# Schematic.net
KiCad netlist of a schematic drawn in Altium Designer
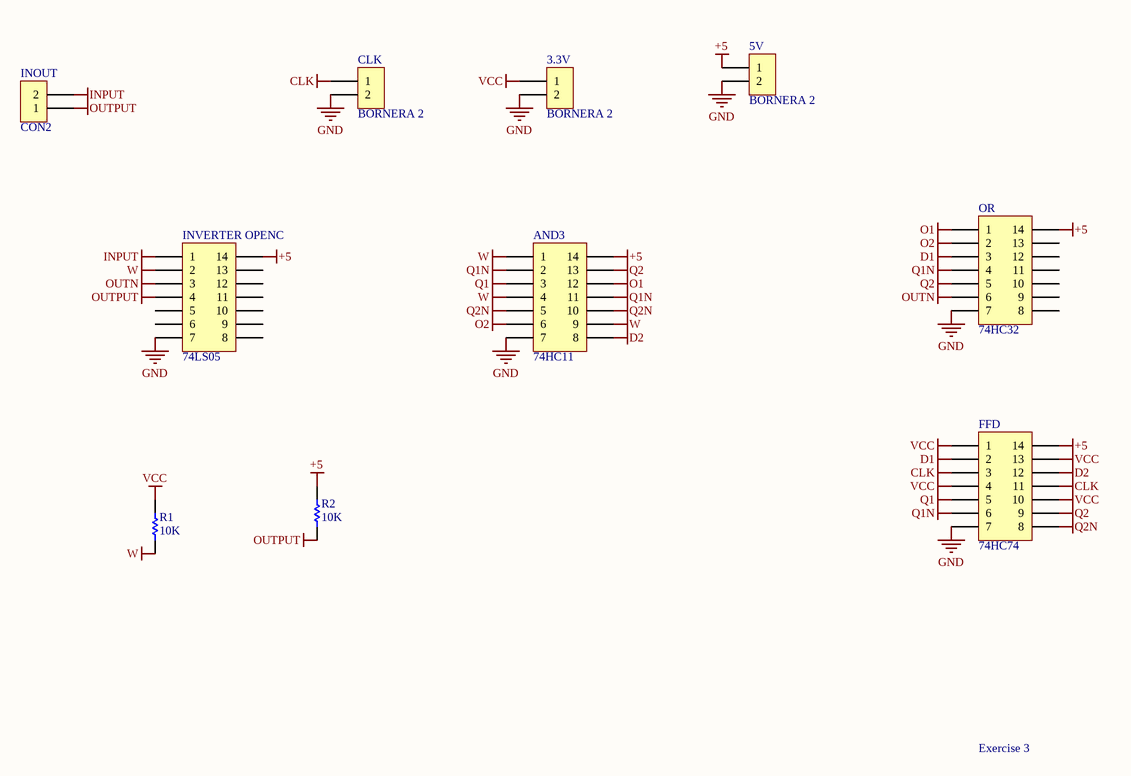
[diagram p0: Schematic.SchDoc]

(export (version "E")
  (design (tool "Eeschema 10.0.6"))
  (components
    (comp (ref "3.3V")
      (value "BORNERA 2")
      (footprint "BORNERA2")
      (libsource (lib "LIBEBAL") (part "BORNERA 2"))
    )
    (comp (ref "5V")
      (value "BORNERA 2")
      (footprint "BORNERA2")
      (libsource (lib "LIBEBAL") (part "BORNERA 2"))
    )
    (comp (ref "AND3") (value "74HC11") (footprint "DIP14") (libsource (lib "LIBEBAL") (part "IC_DIP14")))
    (comp (ref "CLK")
      (value "BORNERA 2")
      (footprint "BORNERA2")
      (libsource (lib "LIBEBAL") (part "BORNERA 2"))
    )
    (comp (ref "FFD") (value "74HC74") (footprint "DIP14") (libsource (lib "LIBEBAL") (part "IC_DIP14")))
    (comp (ref "INOUT") (value "CON2") (footprint "SIP2") (libsource (lib "LIBEBAL") (part "CON2")))
    (comp (ref "INVERTER OPENC")
      (value "74LS05")
      (footprint "DIP14")
      (libsource (lib "LIBEBAL") (part "IC_DIP14"))
    )
    (comp (ref "OR") (value "74HC32") (footprint "DIP14") (libsource (lib "LIBEBAL") (part "IC_DIP14")))
    (comp (ref "R1") (value "10K") (footprint "RES400") (libsource (lib "LIBEBAL") (part "RES")))
    (comp (ref "R2") (value "10K") (footprint "RES400") (libsource (lib "LIBEBAL") (part "RES")))
  )
  (nets
    (net (code "1") (name "+5") (class "Default")
      (node (ref "5V") (pin "1") (pinfunction "1_1") (pintype "passive"))
      (node (ref "AND3") (pin "14") (pinfunction "14_14") (pintype "passive"))
      (node (ref "FFD") (pin "14") (pinfunction "14_14") (pintype "passive"))
      (node (ref "INVERTER OPENC") (pin "14") (pinfunction "14_14") (pintype "passive"))
      (node (ref "OR") (pin "14") (pinfunction "14_14") (pintype "passive"))
      (node (ref "R2") (pin "2") (pinfunction "2_2") (pintype "passive"))
    )
    (net (code "2") (name "CLK") (class "Default")
      (node (ref "CLK") (pin "1") (pinfunction "1_1") (pintype "passive"))
      (node (ref "FFD") (pin "11") (pinfunction "11_11") (pintype "passive"))
      (node (ref "FFD") (pin "3") (pinfunction "3_3") (pintype "passive"))
    )
    (net (code "3") (name "D1") (class "Default")
      (node (ref "FFD") (pin "2") (pinfunction "2_2") (pintype "passive"))
      (node (ref "OR") (pin "3") (pinfunction "3_3") (pintype "passive"))
    )
    (net (code "4") (name "D2") (class "Default")
      (node (ref "AND3") (pin "8") (pinfunction "8_8") (pintype "passive"))
      (node (ref "FFD") (pin "12") (pinfunction "12_12") (pintype "passive"))
    )
    (net (code "5") (name "GND") (class "Default")
      (node (ref "3.3V") (pin "2") (pinfunction "2_2") (pintype "passive"))
      (node (ref "5V") (pin "2") (pinfunction "2_2") (pintype "passive"))
      (node (ref "AND3") (pin "7") (pinfunction "7_7") (pintype "passive"))
      (node (ref "CLK") (pin "2") (pinfunction "2_2") (pintype "passive"))
      (node (ref "FFD") (pin "7") (pinfunction "7_7") (pintype "passive"))
      (node (ref "INVERTER OPENC") (pin "7") (pinfunction "7_7") (pintype "passive"))
      (node (ref "OR") (pin "7") (pinfunction "7_7") (pintype "passive"))
    )
    (net (code "6") (name "INPUT") (class "Default")
      (node (ref "INOUT") (pin "2") (pinfunction "2_2") (pintype "passive"))
      (node (ref "INVERTER OPENC") (pin "1") (pinfunction "1_1") (pintype "passive"))
    )
    (net (code "7") (name "O1") (class "Default")
      (node (ref "AND3") (pin "12") (pinfunction "12_12") (pintype "passive"))
      (node (ref "OR") (pin "1") (pinfunction "1_1") (pintype "passive"))
    )
    (net (code "8") (name "O2") (class "Default")
      (node (ref "AND3") (pin "6") (pinfunction "6_6") (pintype "passive"))
      (node (ref "OR") (pin "2") (pinfunction "2_2") (pintype "passive"))
    )
    (net (code "9") (name "OUTN") (class "Default")
      (node (ref "INVERTER OPENC") (pin "3") (pinfunction "3_3") (pintype "passive"))
      (node (ref "OR") (pin "6") (pinfunction "6_6") (pintype "passive"))
    )
    (net (code "10") (name "OUTPUT") (class "Default")
      (node (ref "INOUT") (pin "1") (pinfunction "1_1") (pintype "passive"))
      (node (ref "INVERTER OPENC") (pin "4") (pinfunction "4_4") (pintype "passive"))
      (node (ref "R2") (pin "1") (pinfunction "1_1") (pintype "passive"))
    )
    (net (code "11") (name "Q1") (class "Default")
      (node (ref "AND3") (pin "3") (pinfunction "3_3") (pintype "passive"))
      (node (ref "FFD") (pin "5") (pinfunction "5_5") (pintype "passive"))
    )
    (net (code "12") (name "Q1N") (class "Default")
      (node (ref "AND3") (pin "11") (pinfunction "11_11") (pintype "passive"))
      (node (ref "AND3") (pin "2") (pinfunction "2_2") (pintype "passive"))
      (node (ref "FFD") (pin "6") (pinfunction "6_6") (pintype "passive"))
      (node (ref "OR") (pin "4") (pinfunction "4_4") (pintype "passive"))
    )
    (net (code "13") (name "Q2") (class "Default")
      (node (ref "AND3") (pin "13") (pinfunction "13_13") (pintype "passive"))
      (node (ref "FFD") (pin "9") (pinfunction "9_9") (pintype "passive"))
      (node (ref "OR") (pin "5") (pinfunction "5_5") (pintype "passive"))
    )
    (net (code "14") (name "Q2N") (class "Default")
      (node (ref "AND3") (pin "10") (pinfunction "10_10") (pintype "passive"))
      (node (ref "AND3") (pin "5") (pinfunction "5_5") (pintype "passive"))
      (node (ref "FFD") (pin "8") (pinfunction "8_8") (pintype "passive"))
    )
    (net (code "15") (name "VCC") (class "Default")
      (node (ref "3.3V") (pin "1") (pinfunction "1_1") (pintype "passive"))
      (node (ref "FFD") (pin "1") (pinfunction "1_1") (pintype "passive"))
      (node (ref "FFD") (pin "10") (pinfunction "10_10") (pintype "passive"))
      (node (ref "FFD") (pin "13") (pinfunction "13_13") (pintype "passive"))
      (node (ref "FFD") (pin "4") (pinfunction "4_4") (pintype "passive"))
      (node (ref "R1") (pin "2") (pinfunction "2_2") (pintype "passive"))
    )
    (net (code "16") (name "W") (class "Default")
      (node (ref "AND3") (pin "1") (pinfunction "1_1") (pintype "passive"))
      (node (ref "AND3") (pin "4") (pinfunction "4_4") (pintype "passive"))
      (node (ref "AND3") (pin "9") (pinfunction "9_9") (pintype "passive"))
      (node (ref "INVERTER OPENC") (pin "2") (pinfunction "2_2") (pintype "passive"))
      (node (ref "R1") (pin "1") (pinfunction "1_1") (pintype "passive"))
    )
    (net (code "17") (name "unconnected-(INVERTER OPENC-Pad5)") (class "Default")
      (node (ref "INVERTER OPENC") (pin "5") (pinfunction "5_5") (pintype "passive"))
    )
    (net (code "18") (name "unconnected-(INVERTER OPENC-Pad6)") (class "Default")
      (node (ref "INVERTER OPENC") (pin "6") (pinfunction "6_6") (pintype "passive"))
    )
    (net (code "19") (name "unconnected-(INVERTER OPENC-Pad8)") (class "Default")
      (node (ref "INVERTER OPENC") (pin "8") (pinfunction "8_8") (pintype "passive"))
    )
    (net (code "20") (name "unconnected-(INVERTER OPENC-Pad9)") (class "Default")
      (node (ref "INVERTER OPENC") (pin "9") (pinfunction "9_9") (pintype "passive"))
    )
    (net (code "21") (name "unconnected-(INVERTER OPENC-Pad10)") (class "Default")
      (node (ref "INVERTER OPENC") (pin "10") (pinfunction "10_10") (pintype "passive"))
    )
    (net (code "22") (name "unconnected-(INVERTER OPENC-Pad11)") (class "Default")
      (node (ref "INVERTER OPENC") (pin "11") (pinfunction "11_11") (pintype "passive"))
    )
    (net (code "23") (name "unconnected-(INVERTER OPENC-Pad12)") (class "Default")
      (node (ref "INVERTER OPENC") (pin "12") (pinfunction "12_12") (pintype "passive"))
    )
    (net (code "24") (name "unconnected-(INVERTER OPENC-Pad13)") (class "Default")
      (node (ref "INVERTER OPENC") (pin "13") (pinfunction "13_13") (pintype "passive"))
    )
    (net (code "25") (name "unconnected-(OR-Pad8)") (class "Default")
      (node (ref "OR") (pin "8") (pinfunction "8_8") (pintype "passive"))
    )
    (net (code "26") (name "unconnected-(OR-Pad9)") (class "Default")
      (node (ref "OR") (pin "9") (pinfunction "9_9") (pintype "passive"))
    )
    (net (code "27") (name "unconnected-(OR-Pad10)") (class "Default")
      (node (ref "OR") (pin "10") (pinfunction "10_10") (pintype "passive"))
    )
    (net (code "28") (name "unconnected-(OR-Pad11)") (class "Default")
      (node (ref "OR") (pin "11") (pinfunction "11_11") (pintype "passive"))
    )
    (net (code "29") (name "unconnected-(OR-Pad12)") (class "Default")
      (node (ref "OR") (pin "12") (pinfunction "12_12") (pintype "passive"))
    )
    (net (code "30") (name "unconnected-(OR-Pad13)") (class "Default")
      (node (ref "OR") (pin "13") (pinfunction "13_13") (pintype "passive"))
    )
  )
)
